# Board_1.net
KiCad netlist of a schematic drawn in EAGLE
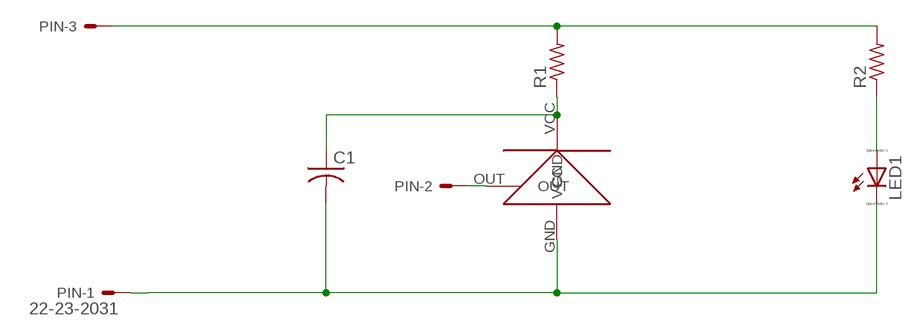
[diagram p0: schematic, sheet 1]

(export (version "E")
  (design (tool "Eeschema 10.0.6"))
  (components
    (comp (ref "C1")
      (value "C-USC0805")
      (footprint "eagle-import:C0805")
      (libsource (lib "eagle-import") (part "C-USC0805"))
    )
    (comp (ref "LED1")
      (value "LED_ELD260")
      (footprint "eagle-import:LED_LD260")
      (libsource (lib "eagle-import") (part "LED_ELD260"))
    )
    (comp (ref "PIN")
      (value "22-23-2031")
      (footprint "eagle-import:22-23-2031")
      (fields (field (name "MF") "MOLEX"))
      (libsource (lib "eagle-import") (part "22-23-2031"))
    )
    (comp (ref "R1")
      (value "R-US_R0805")
      (footprint "eagle-import:R0805")
      (libsource (lib "eagle-import") (part "R-US_R0805"))
    )
    (comp (ref "R2")
      (value "R-US_R0805")
      (footprint "eagle-import:R0805")
      (libsource (lib "eagle-import") (part "R-US_R0805"))
    )
    (comp (ref "U$1")
      (value "TSOP38238")
      (footprint "eagle-import:TSOP38238")
      (libsource (lib "eagle-import") (part "TSOP38238"))
    )
  )
  (nets
    (net (code "1") (name "Net-(C1-Pad1)") (class "Default")
      (node (ref "C1") (pin "1") (pinfunction "1_1") (pintype "passive"))
      (node (ref "R1") (pin "1") (pinfunction "1_1") (pintype "passive"))
      (node (ref "U$1") (pin "VCC") (pinfunction "VCC_VCC") (pintype "bidirectional"))
    )
    (net (code "2") (name "Net-(LED1-C)") (class "Default")
      (node (ref "C1") (pin "2") (pinfunction "2_2") (pintype "passive"))
      (node (ref "LED1") (pin "K") (pinfunction "C_K") (pintype "passive"))
      (node (ref "PIN") (pin "1") (pinfunction "S_1") (pintype "passive"))
      (node (ref "U$1") (pin "GND") (pinfunction "GND_GND") (pintype "bidirectional"))
    )
    (net (code "3") (name "Net-(LED1-PadA)") (class "Default")
      (node (ref "LED1") (pin "A") (pinfunction "A_A") (pintype "passive"))
      (node (ref "R2") (pin "1") (pinfunction "1_1") (pintype "passive"))
    )
    (net (code "4") (name "Net-(PINB-S)") (class "Default")
      (node (ref "PIN") (pin "2") (pinfunction "S_2") (pintype "passive"))
      (node (ref "U$1") (pin "OUT") (pinfunction "OUT_OUT") (pintype "bidirectional"))
    )
    (net (code "5") (name "Net-(PINC-S)") (class "Default")
      (node (ref "PIN") (pin "3") (pinfunction "S_3") (pintype "passive"))
      (node (ref "R1") (pin "2") (pinfunction "2_2") (pintype "passive"))
      (node (ref "R2") (pin "2") (pinfunction "2_2") (pintype "passive"))
    )
  )
)
